# Qunyin_mmWave_mainPowers.net
KiCad netlist of a schematic drawn in Altium Designer
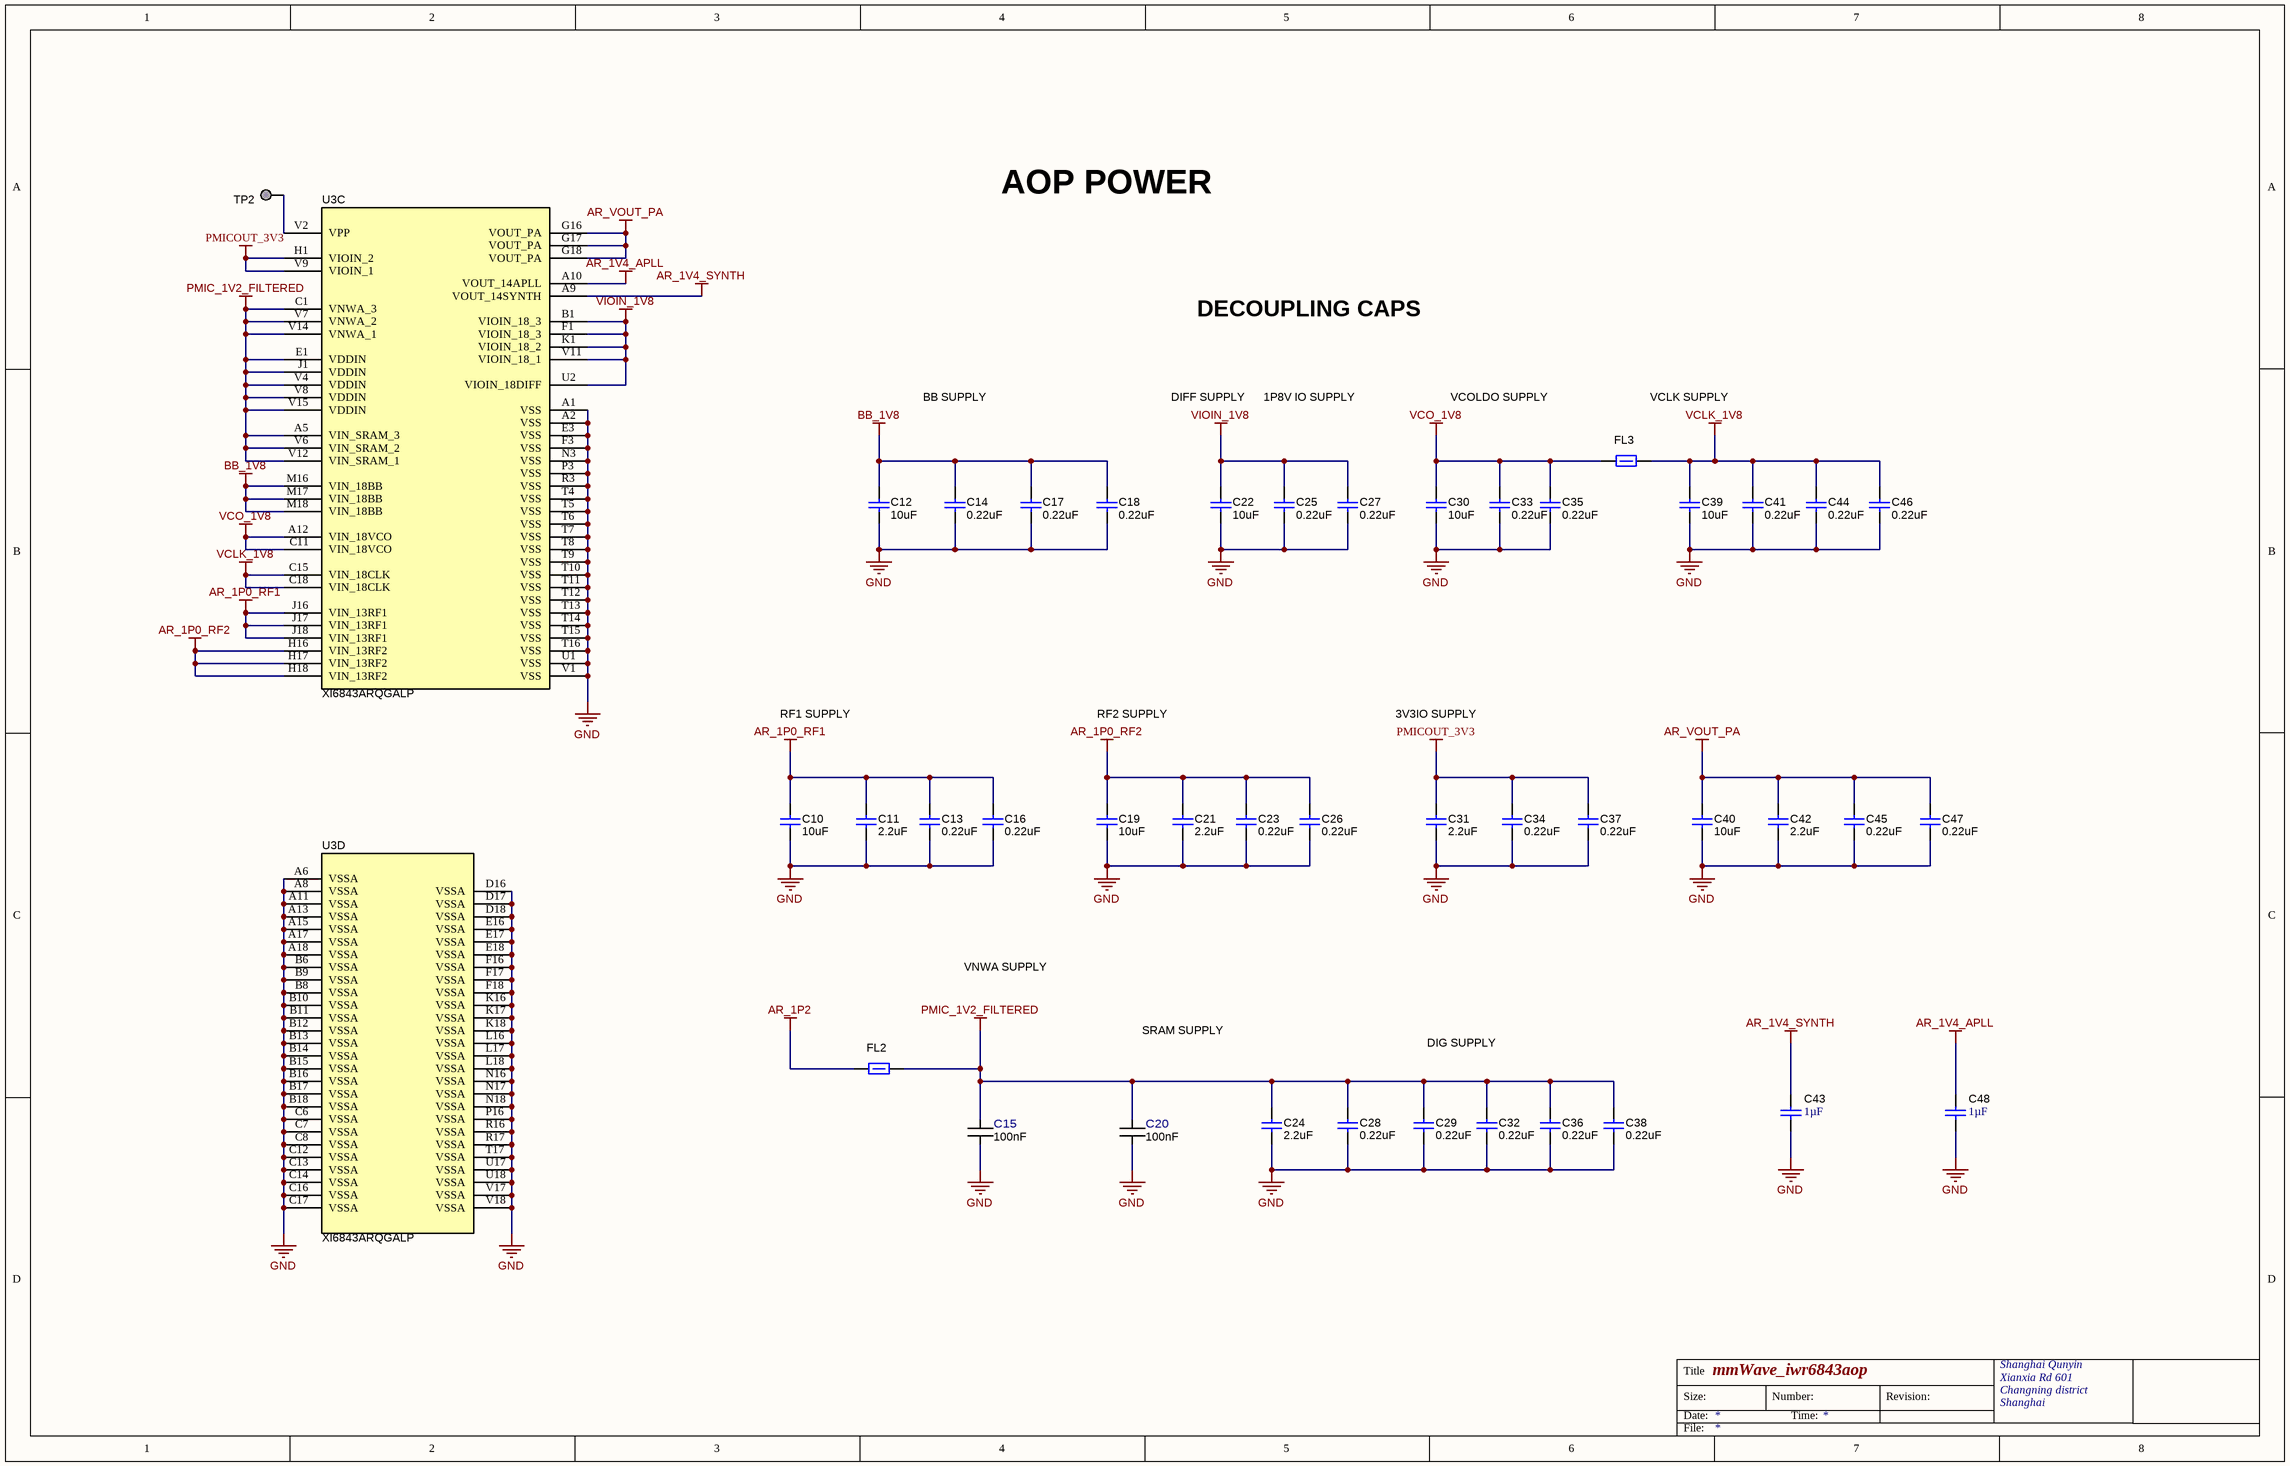
[diagram p0: Qunyin_mmWave_mainPowers.SchDoc]

(export (version "E")
  (design (tool "Eeschema 10.0.6"))
  (components
    (comp (ref "C10")
      (value "10uF")
      (footprint "0402_070")
      (description "CAP, CERM, 10 uF, 10 V, +/- 20%, X5R, 0402")
      (fields
        (field (name "MANUFACTURER") "Samsung Electro-Mechanics")
        (field (name "PARTNUMBER") "CL05A106MP5NUNC")
      )
      (libsource (lib "Altium Vault - TI") (part "Capacitor"))
    )
    (comp (ref "C11")
      (value "2.2uF")
      (footprint "0201L")
      (description "CAP, CERM, 2.2 uF, 6.3 V, +/- 20%, X5R, 0201")
      (fields
        (field (name "MANUFACTURER") "Samsung Electro-Mechanics")
        (field (name "PARTNUMBER") "CL03A225MQ3CRNC")
        (field (name "PUBLISHER") "Texas Instruments")
      )
      (libsource (lib "Altium Vault - TI") (part "Capacitor"))
    )
    (comp (ref "C12")
      (value "10uF")
      (footprint "0402_070")
      (description "CAP, CERM, 10 uF, 10 V, +/- 20%, X5R, 0402")
      (fields
        (field (name "MANUFACTURER") "Samsung Electro-Mechanics")
        (field (name "PARTNUMBER") "CL05A106MP5NUNC")
      )
      (libsource (lib "Altium Vault - TI") (part "Capacitor"))
    )
    (comp (ref "C13")
      (value "0.22uF")
      (footprint "0201_033L")
      (description "CAP, CERM, 0.22 uF, 10 V, +/- 20%, X5R, 0201")
      (fields
        (field (name "MANUFACTURER") "Taiyo Yuden")
        (field (name "PARTNUMBER") "LMK063BJ224MP-F")
        (field (name "PUBLISHER") "Texas Instruments")
      )
      (libsource (lib "Altium Vault - TI") (part "Capacitor"))
    )
    (comp (ref "C14")
      (value "0.22uF")
      (footprint "0201_033L")
      (description "CAP, CERM, 0.22 uF, 10 V, +/- 20%, X5R, 0201")
      (fields
        (field (name "MANUFACTURER") "Taiyo Yuden")
        (field (name "PARTNUMBER") "LMK063BJ224MP-F")
        (field (name "PUBLISHER") "Texas Instruments")
      )
      (libsource (lib "Altium Vault - TI") (part "Capacitor"))
    )
    (comp (ref "C15")
      (value "GRM033R6YA104KE14D")
      (footprint "FP-GRM033R6YA104KE14D_0201 (0603 Metric)-IPC_C")
      (description "Cap Ceramic 0.1uF 35V X5R 10% Pad SMD 0201 85C T/R")
      (fields (field (name "CAP_F") "100nF") (field (name "MANUFACTURER") "Murata Electronics North America"))
      (libsource (lib "Altium Vault - TI") (part "SYM-B32642B0223J"))
    )
    (comp (ref "C16")
      (value "0.22uF")
      (footprint "0201_033L")
      (description "CAP, CERM, 0.22 uF, 10 V, +/- 20%, X5R, 0201")
      (fields
        (field (name "MANUFACTURER") "Taiyo Yuden")
        (field (name "PARTNUMBER") "LMK063BJ224MP-F")
        (field (name "PUBLISHER") "Texas Instruments")
      )
      (libsource (lib "Altium Vault - TI") (part "Capacitor"))
    )
    (comp (ref "C17")
      (value "0.22uF")
      (footprint "0201_033L")
      (description "CAP, CERM, 0.22 uF, 10 V, +/- 20%, X5R, 0201")
      (fields
        (field (name "MANUFACTURER") "Taiyo Yuden")
        (field (name "PARTNUMBER") "LMK063BJ224MP-F")
        (field (name "PUBLISHER") "Texas Instruments")
      )
      (libsource (lib "Altium Vault - TI") (part "Capacitor"))
    )
    (comp (ref "C18")
      (value "0.22uF")
      (footprint "0201_033L")
      (description "CAP, CERM, 0.22 uF, 10 V, +/- 20%, X5R, 0201")
      (fields
        (field (name "MANUFACTURER") "Taiyo Yuden")
        (field (name "PARTNUMBER") "LMK063BJ224MP-F")
        (field (name "PUBLISHER") "Texas Instruments")
      )
      (libsource (lib "Altium Vault - TI") (part "Capacitor"))
    )
    (comp (ref "C19")
      (value "10uF")
      (footprint "0402_070")
      (description "CAP, CERM, 10 uF, 10 V, +/- 20%, X5R, 0402")
      (fields
        (field (name "MANUFACTURER") "Samsung Electro-Mechanics")
        (field (name "PARTNUMBER") "CL05A106MP5NUNC")
      )
      (libsource (lib "Altium Vault - TI") (part "Capacitor"))
    )
    (comp (ref "C20")
      (value "GRM033R6YA104KE14D")
      (footprint "FP-GRM033R6YA104KE14D_0201 (0603 Metric)-IPC_C")
      (description "Cap Ceramic 0.1uF 35V X5R 10% Pad SMD 0201 85C T/R")
      (fields (field (name "CAP_F") "100nF") (field (name "MANUFACTURER") "Murata Electronics North America"))
      (libsource (lib "Altium Vault - TI") (part "SYM-B32642B0223J"))
    )
    (comp (ref "C21")
      (value "2.2uF")
      (footprint "0201L")
      (description "CAP, CERM, 2.2 uF, 6.3 V, +/- 20%, X5R, 0201")
      (fields
        (field (name "MANUFACTURER") "Samsung Electro-Mechanics")
        (field (name "PARTNUMBER") "CL03A225MQ3CRNC")
        (field (name "PUBLISHER") "Texas Instruments")
      )
      (libsource (lib "Altium Vault - TI") (part "Capacitor"))
    )
    (comp (ref "C22")
      (value "10uF")
      (footprint "0402_070")
      (description "CAP, CERM, 10 uF, 10 V, +/- 20%, X5R, 0402")
      (fields
        (field (name "MANUFACTURER") "Samsung Electro-Mechanics")
        (field (name "PARTNUMBER") "CL05A106MP5NUNC")
      )
      (libsource (lib "Altium Vault - TI") (part "Capacitor"))
    )
    (comp (ref "C23")
      (value "0.22uF")
      (footprint "0201_033L")
      (description "CAP, CERM, 0.22 uF, 10 V, +/- 20%, X5R, 0201")
      (fields
        (field (name "MANUFACTURER") "Taiyo Yuden")
        (field (name "PARTNUMBER") "LMK063BJ224MP-F")
        (field (name "PUBLISHER") "Texas Instruments")
      )
      (libsource (lib "Altium Vault - TI") (part "Capacitor"))
    )
    (comp (ref "C24")
      (value "2.2uF")
      (footprint "0201L")
      (description "CAP, CERM, 2.2 uF, 6.3 V, +/- 20%, X5R, 0201")
      (fields
        (field (name "MANUFACTURER") "Samsung Electro-Mechanics")
        (field (name "PARTNUMBER") "CL03A225MQ3CRNC")
        (field (name "PUBLISHER") "Texas Instruments")
      )
      (libsource (lib "Altium Vault - TI") (part "Capacitor"))
    )
    (comp (ref "C25")
      (value "0.22uF")
      (footprint "0201_033L")
      (description "CAP, CERM, 0.22 uF, 10 V, +/- 20%, X5R, 0201")
      (fields
        (field (name "MANUFACTURER") "Taiyo Yuden")
        (field (name "PARTNUMBER") "LMK063BJ224MP-F")
        (field (name "PUBLISHER") "Texas Instruments")
      )
      (libsource (lib "Altium Vault - TI") (part "Capacitor"))
    )
    (comp (ref "C26")
      (value "0.22uF")
      (footprint "0201_033L")
      (description "CAP, CERM, 0.22 uF, 10 V, +/- 20%, X5R, 0201")
      (fields
        (field (name "MANUFACTURER") "Taiyo Yuden")
        (field (name "PARTNUMBER") "LMK063BJ224MP-F")
        (field (name "PUBLISHER") "Texas Instruments")
      )
      (libsource (lib "Altium Vault - TI") (part "Capacitor"))
    )
    (comp (ref "C27")
      (value "0.22uF")
      (footprint "0201_033L")
      (description "CAP, CERM, 0.22 uF, 10 V, +/- 20%, X5R, 0201")
      (fields
        (field (name "MANUFACTURER") "Taiyo Yuden")
        (field (name "PARTNUMBER") "LMK063BJ224MP-F")
        (field (name "PUBLISHER") "Texas Instruments")
      )
      (libsource (lib "Altium Vault - TI") (part "Capacitor"))
    )
    (comp (ref "C28")
      (value "0.22uF")
      (footprint "0201_033L")
      (description "CAP, CERM, 0.22 uF, 10 V, +/- 20%, X5R, 0201")
      (fields
        (field (name "MANUFACTURER") "Taiyo Yuden")
        (field (name "PARTNUMBER") "LMK063BJ224MP-F")
        (field (name "PUBLISHER") "Texas Instruments")
      )
      (libsource (lib "Altium Vault - TI") (part "Capacitor"))
    )
    (comp (ref "C29")
      (value "0.22uF")
      (footprint "0201_033L")
      (description "CAP, CERM, 0.22 uF, 10 V, +/- 20%, X5R, 0201")
      (fields
        (field (name "MANUFACTURER") "Taiyo Yuden")
        (field (name "PARTNUMBER") "LMK063BJ224MP-F")
        (field (name "PUBLISHER") "Texas Instruments")
      )
      (libsource (lib "Altium Vault - TI") (part "Capacitor"))
    )
    (comp (ref "C30")
      (value "10uF")
      (footprint "0402_070")
      (description "CAP, CERM, 10 uF, 10 V, +/- 20%, X5R, 0402")
      (fields
        (field (name "MANUFACTURER") "Samsung Electro-Mechanics")
        (field (name "PARTNUMBER") "CL05A106MP5NUNC")
      )
      (libsource (lib "Altium Vault - TI") (part "Capacitor"))
    )
    (comp (ref "C31")
      (value "2.2uF")
      (footprint "0201L")
      (description "CAP, CERM, 2.2 uF, 6.3 V, +/- 20%, X5R, 0201")
      (fields
        (field (name "MANUFACTURER") "Samsung Electro-Mechanics")
        (field (name "PARTNUMBER") "CL03A225MQ3CRNC")
        (field (name "PUBLISHER") "Texas Instruments")
      )
      (libsource (lib "Altium Vault - TI") (part "Capacitor"))
    )
    (comp (ref "C32")
      (value "0.22uF")
      (footprint "0201_033L")
      (description "CAP, CERM, 0.22 uF, 10 V, +/- 20%, X5R, 0201")
      (fields
        (field (name "MANUFACTURER") "Taiyo Yuden")
        (field (name "PARTNUMBER") "LMK063BJ224MP-F")
        (field (name "PUBLISHER") "Texas Instruments")
      )
      (libsource (lib "Altium Vault - TI") (part "Capacitor"))
    )
    (comp (ref "C33")
      (value "0.22uF")
      (footprint "0201_033L")
      (description "CAP, CERM, 0.22 uF, 10 V, +/- 20%, X5R, 0201")
      (fields
        (field (name "MANUFACTURER") "Taiyo Yuden")
        (field (name "PARTNUMBER") "LMK063BJ224MP-F")
        (field (name "PUBLISHER") "Texas Instruments")
      )
      (libsource (lib "Altium Vault - TI") (part "Capacitor"))
    )
    (comp (ref "C34")
      (value "0.22uF")
      (footprint "0201_033L")
      (description "CAP, CERM, 0.22 uF, 10 V, +/- 20%, X5R, 0201")
      (fields
        (field (name "MANUFACTURER") "Taiyo Yuden")
        (field (name "PARTNUMBER") "LMK063BJ224MP-F")
        (field (name "PUBLISHER") "Texas Instruments")
      )
      (libsource (lib "Altium Vault - TI") (part "Capacitor"))
    )
    (comp (ref "C35")
      (value "0.22uF")
      (footprint "0201_033L")
      (description "CAP, CERM, 0.22 uF, 10 V, +/- 20%, X5R, 0201")
      (fields
        (field (name "MANUFACTURER") "Taiyo Yuden")
        (field (name "PARTNUMBER") "LMK063BJ224MP-F")
        (field (name "PUBLISHER") "Texas Instruments")
      )
      (libsource (lib "Altium Vault - TI") (part "Capacitor"))
    )
    (comp (ref "C36")
      (value "0.22uF")
      (footprint "0201_033L")
      (description "CAP, CERM, 0.22 uF, 10 V, +/- 20%, X5R, 0201")
      (fields
        (field (name "MANUFACTURER") "Taiyo Yuden")
        (field (name "PARTNUMBER") "LMK063BJ224MP-F")
        (field (name "PUBLISHER") "Texas Instruments")
      )
      (libsource (lib "Altium Vault - TI") (part "Capacitor"))
    )
    (comp (ref "C37")
      (value "0.22uF")
      (footprint "0201_033L")
      (description "CAP, CERM, 0.22 uF, 10 V, +/- 20%, X5R, 0201")
      (fields
        (field (name "MANUFACTURER") "Taiyo Yuden")
        (field (name "PARTNUMBER") "LMK063BJ224MP-F")
        (field (name "PUBLISHER") "Texas Instruments")
      )
      (libsource (lib "Altium Vault - TI") (part "Capacitor"))
    )
    (comp (ref "C38")
      (value "0.22uF")
      (footprint "0201_033L")
      (description "CAP, CERM, 0.22 uF, 10 V, +/- 20%, X5R, 0201")
      (fields
        (field (name "MANUFACTURER") "Taiyo Yuden")
        (field (name "PARTNUMBER") "LMK063BJ224MP-F")
        (field (name "PUBLISHER") "Texas Instruments")
      )
      (libsource (lib "Altium Vault - TI") (part "Capacitor"))
    )
    (comp (ref "C39")
      (value "10uF")
      (footprint "0402_070")
      (description "CAP, CERM, 10 uF, 10 V, +/- 20%, X5R, 0402")
      (fields
        (field (name "MANUFACTURER") "Samsung Electro-Mechanics")
        (field (name "PARTNUMBER") "CL05A106MP5NUNC")
      )
      (libsource (lib "Altium Vault - TI") (part "Capacitor"))
    )
    (comp (ref "C40")
      (value "10uF")
      (footprint "0402_070")
      (description "CAP, CERM, 10 uF, 10 V, +/- 20%, X5R, 0402")
      (fields
        (field (name "MANUFACTURER") "Samsung Electro-Mechanics")
        (field (name "PARTNUMBER") "CL05A106MP5NUNC")
      )
      (libsource (lib "Altium Vault - TI") (part "Capacitor"))
    )
    (comp (ref "C41")
      (value "0.22uF")
      (footprint "0201_033L")
      (description "CAP, CERM, 0.22 uF, 10 V, +/- 20%, X5R, 0201")
      (fields
        (field (name "MANUFACTURER") "Taiyo Yuden")
        (field (name "PARTNUMBER") "LMK063BJ224MP-F")
        (field (name "PUBLISHER") "Texas Instruments")
      )
      (libsource (lib "Altium Vault - TI") (part "Capacitor"))
    )
    (comp (ref "C42")
      (value "2.2uF")
      (footprint "0201L")
      (description "CAP, CERM, 2.2 uF, 6.3 V, +/- 20%, X5R, 0201")
      (fields
        (field (name "MANUFACTURER") "Samsung Electro-Mechanics")
        (field (name "PARTNUMBER") "CL03A225MQ3CRNC")
        (field (name "PUBLISHER") "Texas Instruments")
      )
      (libsource (lib "Altium Vault - TI") (part "Capacitor"))
    )
    (comp (ref "C43")
      (value "CGB2A1X6S0J105K033BC")
      (footprint "0402L")
      (description "CAP, CERM, 1 µF, 6.3 V,+/- 10%, X6S, 0402")
      (fields (field (name "MANUFACTURER") "TDK") (field (name "VALUEDISPLAYED") "1µF"))
      (libsource (lib "Altium Vault - TI") (part "CMP-0081763-1"))
    )
    (comp (ref "C44")
      (value "0.22uF")
      (footprint "0201_033L")
      (description "CAP, CERM, 0.22 uF, 10 V, +/- 20%, X5R, 0201")
      (fields
        (field (name "MANUFACTURER") "Taiyo Yuden")
        (field (name "PARTNUMBER") "LMK063BJ224MP-F")
        (field (name "PUBLISHER") "Texas Instruments")
      )
      (libsource (lib "Altium Vault - TI") (part "Capacitor"))
    )
    (comp (ref "C45")
      (value "0.22uF")
      (footprint "0201_033L")
      (description "CAP, CERM, 0.22 uF, 10 V, +/- 20%, X5R, 0201")
      (fields
        (field (name "MANUFACTURER") "Taiyo Yuden")
        (field (name "PARTNUMBER") "LMK063BJ224MP-F")
        (field (name "PUBLISHER") "Texas Instruments")
      )
      (libsource (lib "Altium Vault - TI") (part "Capacitor"))
    )
    (comp (ref "C46")
      (value "0.22uF")
      (footprint "0201_033L")
      (description "CAP, CERM, 0.22 uF, 10 V, +/- 20%, X5R, 0201")
      (fields
        (field (name "MANUFACTURER") "Taiyo Yuden")
        (field (name "PARTNUMBER") "LMK063BJ224MP-F")
        (field (name "PUBLISHER") "Texas Instruments")
      )
      (libsource (lib "Altium Vault - TI") (part "Capacitor"))
    )
    (comp (ref "C47")
      (value "0.22uF")
      (footprint "0201_033L")
      (description "CAP, CERM, 0.22 uF, 10 V, +/- 20%, X5R, 0201")
      (fields
        (field (name "MANUFACTURER") "Taiyo Yuden")
        (field (name "PARTNUMBER") "LMK063BJ224MP-F")
        (field (name "PUBLISHER") "Texas Instruments")
      )
      (libsource (lib "Altium Vault - TI") (part "Capacitor"))
    )
    (comp (ref "C48")
      (value "CGB2A1X6S0J105K033BC")
      (footprint "0402L")
      (description "CAP, CERM, 1 µF, 6.3 V,+/- 10%, X6S, 0402")
      (fields (field (name "MANUFACTURER") "TDK") (field (name "VALUEDISPLAYED") "1µF"))
      (libsource (lib "Altium Vault - TI") (part "CMP-0081763-1"))
    )
    (comp (ref "FL2")
      (value "BLM15PD300SZ1D")
      (footprint "0402L")
      (description "Inductor, Ferrite Bead, Ferrite, 2.2 A, 0.035 ohm, AEC-Q200 Grade 1, SMD")
      (fields (field (name "MANUFACTURER") "MuRata") (field (name "PUBLISHER") "Texas Instruments"))
      (libsource (lib "Altium Vault - TI") (part "Ferrite_Bead"))
    )
    (comp (ref "FL3")
      (value "BLM15PD300SZ1D")
      (footprint "0402L")
      (description "Inductor, Ferrite Bead, Ferrite, 2.2 A, 0.035 ohm, AEC-Q200 Grade 1, SMD")
      (fields (field (name "MANUFACTURER") "MuRata") (field (name "PUBLISHER") "Texas Instruments"))
      (libsource (lib "Altium Vault - TI") (part "Ferrite_Bead"))
    )
    (comp (ref "TP2")
      (value "TESTPOINT")
      (footprint "TP_25MIL-SMT")
      (description "TEST POINT.  No entry in BOM.")
      (libsource (lib "Altium Vault - TI") (part "TESTPOINT"))
    )
    (comp (ref "U3")
      (value "XI6843ARQGALP")
      (footprint "ALP0180A")
      (description "XI6843ARQGALP, ALP0180A (BGA-180)")
      (fields (field (name "MANUFACTURER") "Texas Instruments") (field (name "PARTNUMBER") "XI6843ARQGALP"))
      (libsource (lib "Altium Vault - TI") (part "XI6843ARQGALP"))
    )
  )
  (nets
    (net (code "1") (name "AR_1P0_RF1") (class "Default")
      (node (ref "C10") (pin "1") (pinfunction "1_1") (pintype "passive"))
      (node (ref "C11") (pin "1") (pinfunction "1_1") (pintype "passive"))
      (node (ref "C13") (pin "1") (pinfunction "1_1") (pintype "passive"))
      (node (ref "C16") (pin "1") (pinfunction "1_1") (pintype "passive"))
      (node (ref "U3") (pin "J16") (pinfunction "VIN_13RF1_J16") (pintype "power_in"))
      (node (ref "U3") (pin "J17") (pinfunction "VIN_13RF1_J17") (pintype "power_in"))
      (node (ref "U3") (pin "J18") (pinfunction "VIN_13RF1_J18") (pintype "power_in"))
    )
    (net (code "2") (name "AR_1P0_RF2") (class "Default")
      (node (ref "C19") (pin "1") (pinfunction "1_1") (pintype "passive"))
      (node (ref "C21") (pin "1") (pinfunction "1_1") (pintype "passive"))
      (node (ref "C23") (pin "1") (pinfunction "1_1") (pintype "passive"))
      (node (ref "C26") (pin "1") (pinfunction "1_1") (pintype "passive"))
      (node (ref "U3") (pin "H16") (pinfunction "VIN_13RF2_H16") (pintype "power_in"))
      (node (ref "U3") (pin "H17") (pinfunction "VIN_13RF2_H17") (pintype "power_in"))
      (node (ref "U3") (pin "H18") (pinfunction "VIN_13RF2_H18") (pintype "power_in"))
    )
    (net (code "3") (name "AR_1P2") (class "Default")
      (node (ref "FL2") (pin "1") (pinfunction "1_1") (pintype "passive"))
    )
    (net (code "4") (name "AR_1V4_APLL") (class "Default")
      (node (ref "C48") (pin "1") (pinfunction "1_1") (pintype "passive"))
      (node (ref "U3") (pin "A10") (pinfunction "VOUT_14APLL_A10") (pintype "power_in"))
    )
    (net (code "5") (name "AR_1V4_SYNTH") (class "Default")
      (node (ref "C43") (pin "1") (pinfunction "1_1") (pintype "passive"))
      (node (ref "U3") (pin "A9") (pinfunction "VOUT_14SYNTH_A9") (pintype "power_in"))
    )
    (net (code "6") (name "AR_VOUT_PA") (class "Default")
      (node (ref "C40") (pin "1") (pinfunction "1_1") (pintype "passive"))
      (node (ref "C42") (pin "1") (pinfunction "1_1") (pintype "passive"))
      (node (ref "C45") (pin "1") (pinfunction "1_1") (pintype "passive"))
      (node (ref "C47") (pin "1") (pinfunction "1_1") (pintype "passive"))
      (node (ref "U3") (pin "G16") (pinfunction "VOUT_PA_G16") (pintype "power_in"))
      (node (ref "U3") (pin "G17") (pinfunction "VOUT_PA_G17") (pintype "power_in"))
      (node (ref "U3") (pin "G18") (pinfunction "VOUT_PA_G18") (pintype "power_in"))
    )
    (net (code "7") (name "BB_1V8") (class "Default")
      (node (ref "C12") (pin "1") (pinfunction "1_1") (pintype "passive"))
      (node (ref "C14") (pin "1") (pinfunction "1_1") (pintype "passive"))
      (node (ref "C17") (pin "1") (pinfunction "1_1") (pintype "passive"))
      (node (ref "C18") (pin "1") (pinfunction "1_1") (pintype "passive"))
      (node (ref "U3") (pin "M16") (pinfunction "VIN_18BB_M16") (pintype "power_in"))
      (node (ref "U3") (pin "M17") (pinfunction "VIN_18BB_M17") (pintype "power_in"))
      (node (ref "U3") (pin "M18") (pinfunction "VIN_18BB_M18") (pintype "power_in"))
    )
    (net (code "8") (name "GND") (class "Default")
      (node (ref "C10") (pin "2") (pinfunction "2_2") (pintype "passive"))
      (node (ref "C11") (pin "2") (pinfunction "2_2") (pintype "passive"))
      (node (ref "C12") (pin "2") (pinfunction "2_2") (pintype "passive"))
      (node (ref "C13") (pin "2") (pinfunction "2_2") (pintype "passive"))
      (node (ref "C14") (pin "2") (pinfunction "2_2") (pintype "passive"))
      (node (ref "C15") (pin "2") (pinfunction "2_2") (pintype "passive"))
      (node (ref "C16") (pin "2") (pinfunction "2_2") (pintype "passive"))
      (node (ref "C17") (pin "2") (pinfunction "2_2") (pintype "passive"))
      (node (ref "C18") (pin "2") (pinfunction "2_2") (pintype "passive"))
      (node (ref "C19") (pin "2") (pinfunction "2_2") (pintype "passive"))
      (node (ref "C20") (pin "2") (pinfunction "2_2") (pintype "passive"))
      (node (ref "C21") (pin "2") (pinfunction "2_2") (pintype "passive"))
      (node (ref "C22") (pin "2") (pinfunction "2_2") (pintype "passive"))
      (node (ref "C23") (pin "2") (pinfunction "2_2") (pintype "passive"))
      (node (ref "C24") (pin "2") (pinfunction "2_2") (pintype "passive"))
      (node (ref "C25") (pin "2") (pinfunction "2_2") (pintype "passive"))
      (node (ref "C26") (pin "2") (pinfunction "2_2") (pintype "passive"))
      (node (ref "C27") (pin "2") (pinfunction "2_2") (pintype "passive"))
      (node (ref "C28") (pin "2") (pinfunction "2_2") (pintype "passive"))
      (node (ref "C29") (pin "2") (pinfunction "2_2") (pintype "passive"))
      (node (ref "C30") (pin "2") (pinfunction "2_2") (pintype "passive"))
      (node (ref "C31") (pin "2") (pinfunction "2_2") (pintype "passive"))
      (node (ref "C32") (pin "2") (pinfunction "2_2") (pintype "passive"))
      (node (ref "C33") (pin "2") (pinfunction "2_2") (pintype "passive"))
      (node (ref "C34") (pin "2") (pinfunction "2_2") (pintype "passive"))
      (node (ref "C35") (pin "2") (pinfunction "2_2") (pintype "passive"))
      (node (ref "C36") (pin "2") (pinfunction "2_2") (pintype "passive"))
      (node (ref "C37") (pin "2") (pinfunction "2_2") (pintype "passive"))
      (node (ref "C38") (pin "2") (pinfunction "2_2") (pintype "passive"))
      (node (ref "C39") (pin "2") (pinfunction "2_2") (pintype "passive"))
      (node (ref "C40") (pin "2") (pinfunction "2_2") (pintype "passive"))
      (node (ref "C41") (pin "2") (pinfunction "2_2") (pintype "passive"))
      (node (ref "C42") (pin "2") (pinfunction "2_2") (pintype "passive"))
      (node (ref "C43") (pin "2") (pinfunction "2_2") (pintype "passive"))
      (node (ref "C44") (pin "2") (pinfunction "2_2") (pintype "passive"))
      (node (ref "C45") (pin "2") (pinfunction "2_2") (pintype "passive"))
      (node (ref "C46") (pin "2") (pinfunction "2_2") (pintype "passive"))
      (node (ref "C47") (pin "2") (pinfunction "2_2") (pintype "passive"))
      (node (ref "C48") (pin "2") (pinfunction "2_2") (pintype "passive"))
      (node (ref "U3") (pin "A1") (pinfunction "VSS_A1") (pintype "power_in"))
      (node (ref "U3") (pin "A11") (pinfunction "VSSA_A11") (pintype "power_in"))
      (node (ref "U3") (pin "A13") (pinfunction "VSSA_A13") (pintype "power_in"))
      (node (ref "U3") (pin "A15") (pinfunction "VSSA_A15") (pintype "power_in"))
      (node (ref "U3") (pin "A17") (pinfunction "VSSA_A17") (pintype "power_in"))
      (node (ref "U3") (pin "A18") (pinfunction "VSSA_A18") (pintype "power_in"))
      (node (ref "U3") (pin "A2") (pinfunction "VSS_A2") (pintype "power_in"))
      (node (ref "U3") (pin "A6") (pinfunction "VSSA_A6") (pintype "power_in"))
      (node (ref "U3") (pin "A8") (pinfunction "VSSA_A8") (pintype "power_in"))
      (node (ref "U3") (pin "B10") (pinfunction "VSSA_B10") (pintype "power_in"))
      (node (ref "U3") (pin "B11") (pinfunction "VSSA_B11") (pintype "power_in"))
      (node (ref "U3") (pin "B12") (pinfunction "VSSA_B12") (pintype "power_in"))
      (node (ref "U3") (pin "B13") (pinfunction "VSSA_B13") (pintype "power_in"))
      (node (ref "U3") (pin "B14") (pinfunction "VSSA_B14") (pintype "power_in"))
      (node (ref "U3") (pin "B15") (pinfunction "VSSA_B15") (pintype "power_in"))
      (node (ref "U3") (pin "B16") (pinfunction "VSSA_B16") (pintype "power_in"))
      (node (ref "U3") (pin "B17") (pinfunction "VSSA_B17") (pintype "power_in"))
      (node (ref "U3") (pin "B18") (pinfunction "VSSA_B18") (pintype "power_in"))
      (node (ref "U3") (pin "B6") (pinfunction "VSSA_B6") (pintype "power_in"))
      (node (ref "U3") (pin "B8") (pinfunction "VSSA_B8") (pintype "power_in"))
      (node (ref "U3") (pin "B9") (pinfunction "VSSA_B9") (pintype "power_in"))
      (node (ref "U3") (pin "C12") (pinfunction "VSSA_C12") (pintype "power_in"))
      (node (ref "U3") (pin "C13") (pinfunction "VSSA_C13") (pintype "power_in"))
      (node (ref "U3") (pin "C14") (pinfunction "VSSA_C14") (pintype "power_in"))
      (node (ref "U3") (pin "C16") (pinfunction "VSSA_C16") (pintype "power_in"))
      (node (ref "U3") (pin "C17") (pinfunction "VSSA_C17") (pintype "power_in"))
      (node (ref "U3") (pin "C6") (pinfunction "VSSA_C6") (pintype "power_in"))
      (node (ref "U3") (pin "C7") (pinfunction "VSSA_C7") (pintype "power_in"))
      (node (ref "U3") (pin "C8") (pinfunction "VSSA_C8") (pintype "power_in"))
      (node (ref "U3") (pin "D16") (pinfunction "VSSA_D16") (pintype "power_in"))
      (node (ref "U3") (pin "D17") (pinfunction "VSSA_D17") (pintype "power_in"))
      (node (ref "U3") (pin "D18") (pinfunction "VSSA_D18") (pintype "power_in"))
      (node (ref "U3") (pin "E16") (pinfunction "VSSA_E16") (pintype "power_in"))
      (node (ref "U3") (pin "E17") (pinfunction "VSSA_E17") (pintype "power_in"))
      (node (ref "U3") (pin "E18") (pinfunction "VSSA_E18") (pintype "power_in"))
      (node (ref "U3") (pin "E3") (pinfunction "VSS_E3") (pintype "power_in"))
      (node (ref "U3") (pin "F16") (pinfunction "VSSA_F16") (pintype "power_in"))
      (node (ref "U3") (pin "F17") (pinfunction "VSSA_F17") (pintype "power_in"))
      (node (ref "U3") (pin "F18") (pinfunction "VSSA_F18") (pintype "power_in"))
      (node (ref "U3") (pin "F3") (pinfunction "VSS_F3") (pintype "power_in"))
      (node (ref "U3") (pin "K16") (pinfunction "VSSA_K16") (pintype "power_in"))
      (node (ref "U3") (pin "K17") (pinfunction "VSSA_K17") (pintype "power_in"))
      (node (ref "U3") (pin "K18") (pinfunction "VSSA_K18") (pintype "power_in"))
      (node (ref "U3") (pin "L16") (pinfunction "VSSA_L16") (pintype "power_in"))
      (node (ref "U3") (pin "L17") (pinfunction "VSSA_L17") (pintype "power_in"))
      (node (ref "U3") (pin "L18") (pinfunction "VSSA_L18") (pintype "power_in"))
      (node (ref "U3") (pin "N16") (pinfunction "VSSA_N16") (pintype "power_in"))
      (node (ref "U3") (pin "N17") (pinfunction "VSSA_N17") (pintype "power_in"))
      (node (ref "U3") (pin "N18") (pinfunction "VSSA_N18") (pintype "power_in"))
      (node (ref "U3") (pin "N3") (pinfunction "VSS_N3") (pintype "power_in"))
      (node (ref "U3") (pin "P16") (pinfunction "VSSA_P16") (pintype "power_in"))
      (node (ref "U3") (pin "P3") (pinfunction "VSS_P3") (pintype "power_in"))
      (node (ref "U3") (pin "R16") (pinfunction "VSSA_R16") (pintype "power_in"))
      (node (ref "U3") (pin "R17") (pinfunction "VSSA_R17") (pintype "power_in"))
      (node (ref "U3") (pin "R3") (pinfunction "VSS_R3") (pintype "power_in"))
      (node (ref "U3") (pin "T10") (pinfunction "VSS_T10") (pintype "power_in"))
      (node (ref "U3") (pin "T11") (pinfunction "VSS_T11") (pintype "power_in"))
      (node (ref "U3") (pin "T12") (pinfunction "VSS_T12") (pintype "power_in"))
      (node (ref "U3") (pin "T13") (pinfunction "VSS_T13") (pintype "power_in"))
      (node (ref "U3") (pin "T14") (pinfunction "VSS_T14") (pintype "power_in"))
      (node (ref "U3") (pin "T15") (pinfunction "VSS_T15") (pintype "power_in"))
      (node (ref "U3") (pin "T16") (pinfunction "VSS_T16") (pintype "power_in"))
      (node (ref "U3") (pin "T17") (pinfunction "VSSA_T17") (pintype "power_in"))
      (node (ref "U3") (pin "T4") (pinfunction "VSS_T4") (pintype "power_in"))
      (node (ref "U3") (pin "T5") (pinfunction "VSS_T5") (pintype "power_in"))
      (node (ref "U3") (pin "T6") (pinfunction "VSS_T6") (pintype "power_in"))
      (node (ref "U3") (pin "T7") (pinfunction "VSS_T7") (pintype "power_in"))
      (node (ref "U3") (pin "T8") (pinfunction "VSS_T8") (pintype "power_in"))
      (node (ref "U3") (pin "T9") (pinfunction "VSS_T9") (pintype "power_in"))
      (node (ref "U3") (pin "U1") (pinfunction "VSS_U1") (pintype "power_in"))
      (node (ref "U3") (pin "U17") (pinfunction "VSSA_U17") (pintype "power_in"))
      (node (ref "U3") (pin "U18") (pinfunction "VSSA_U18") (pintype "power_in"))
      (node (ref "U3") (pin "V1") (pinfunction "VSS_V1") (pintype "power_in"))
      (node (ref "U3") (pin "V17") (pinfunction "VSSA_V17") (pintype "power_in"))
      (node (ref "U3") (pin "V18") (pinfunction "VSSA_V18") (pintype "power_in"))
    )
    (net (code "9") (name "Net-(U3C-VPP)") (class "Default")
      (node (ref "TP2") (pin "1") (pintype "passive"))
      (node (ref "U3") (pin "V2") (pinfunction "VPP_V2") (pintype "power_in"))
    )
    (net (code "10") (name "PMICOUT_3V3") (class "Default")
      (node (ref "C31") (pin "1") (pinfunction "1_1") (pintype "passive"))
      (node (ref "C34") (pin "1") (pinfunction "1_1") (pintype "passive"))
      (node (ref "C37") (pin "1") (pinfunction "1_1") (pintype "passive"))
      (node (ref "U3") (pin "H1") (pinfunction "VIOIN_2_H1") (pintype "power_in"))
      (node (ref "U3") (pin "V9") (pinfunction "VIOIN_1_V9") (pintype "power_in"))
    )
    (net (code "11") (name "PMIC_1V2_FILTERED") (class "Default")
      (node (ref "C15") (pin "1") (pinfunction "1_1") (pintype "passive"))
      (node (ref "C20") (pin "1") (pinfunction "1_1") (pintype "passive"))
      (node (ref "C24") (pin "1") (pinfunction "1_1") (pintype "passive"))
      (node (ref "C28") (pin "1") (pinfunction "1_1") (pintype "passive"))
      (node (ref "C29") (pin "1") (pinfunction "1_1") (pintype "passive"))
      (node (ref "C32") (pin "1") (pinfunction "1_1") (pintype "passive"))
      (node (ref "C36") (pin "1") (pinfunction "1_1") (pintype "passive"))
      (node (ref "C38") (pin "1") (pinfunction "1_1") (pintype "passive"))
      (node (ref "FL2") (pin "2") (pinfunction "2_2") (pintype "passive"))
      (node (ref "U3") (pin "A5") (pinfunction "VIN_SRAM_3_A5") (pintype "power_in"))
      (node (ref "U3") (pin "C1") (pinfunction "VNWA_3_C1") (pintype "power_in"))
      (node (ref "U3") (pin "E1") (pinfunction "VDDIN_E1") (pintype "power_in"))
      (node (ref "U3") (pin "J1") (pinfunction "VDDIN_J1") (pintype "power_in"))
      (node (ref "U3") (pin "V12") (pinfunction "VIN_SRAM_1_V12") (pintype "power_in"))
      (node (ref "U3") (pin "V14") (pinfunction "VNWA_1_V14") (pintype "power_in"))
      (node (ref "U3") (pin "V15") (pinfunction "VDDIN_V15") (pintype "power_in"))
      (node (ref "U3") (pin "V4") (pinfunction "VDDIN_V4") (pintype "power_in"))
      (node (ref "U3") (pin "V6") (pinfunction "VIN_SRAM_2_V6") (pintype "power_in"))
      (node (ref "U3") (pin "V7") (pinfunction "VNWA_2_V7") (pintype "power_in"))
      (node (ref "U3") (pin "V8") (pinfunction "VDDIN_V8") (pintype "power_in"))
    )
    (net (code "12") (name "VCLK_1V8") (class "Default")
      (node (ref "C39") (pin "1") (pinfunction "1_1") (pintype "passive"))
      (node (ref "C41") (pin "1") (pinfunction "1_1") (pintype "passive"))
      (node (ref "C44") (pin "1") (pinfunction "1_1") (pintype "passive"))
      (node (ref "C46") (pin "1") (pinfunction "1_1") (pintype "passive"))
      (node (ref "FL3") (pin "2") (pinfunction "2_2") (pintype "passive"))
      (node (ref "U3") (pin "C15") (pinfunction "VIN_18CLK_C15") (pintype "power_in"))
      (node (ref "U3") (pin "C18") (pinfunction "VIN_18CLK_C18") (pintype "power_in"))
    )
    (net (code "13") (name "VCO_1V8") (class "Default")
      (node (ref "C30") (pin "1") (pinfunction "1_1") (pintype "passive"))
      (node (ref "C33") (pin "1") (pinfunction "1_1") (pintype "passive"))
      (node (ref "C35") (pin "1") (pinfunction "1_1") (pintype "passive"))
      (node (ref "FL3") (pin "1") (pinfunction "1_1") (pintype "passive"))
      (node (ref "U3") (pin "A12") (pinfunction "VIN_18VCO_A12") (pintype "power_in"))
      (node (ref "U3") (pin "C11") (pinfunction "VIN_18VCO_C11") (pintype "power_in"))
    )
    (net (code "14") (name "VIOIN_1V8") (class "Default")
      (node (ref "C22") (pin "1") (pinfunction "1_1") (pintype "passive"))
      (node (ref "C25") (pin "1") (pinfunction "1_1") (pintype "passive"))
      (node (ref "C27") (pin "1") (pinfunction "1_1") (pintype "passive"))
      (node (ref "U3") (pin "B1") (pinfunction "VIOIN_18_3_B1") (pintype "power_in"))
      (node (ref "U3") (pin "F1") (pinfunction "VIOIN_18_3_F1") (pintype "power_in"))
      (node (ref "U3") (pin "K1") (pinfunction "VIOIN_18_2_K1") (pintype "power_in"))
      (node (ref "U3") (pin "U2") (pinfunction "VIOIN_18DIFF_U2") (pintype "power_in"))
      (node (ref "U3") (pin "V11") (pinfunction "VIOIN_18_1_V11") (pintype "power_in"))
    )
  )
)
